# PolarStormControlBoard_smol_275_gnd.net
KiCad netlist of a schematic drawn in EAGLE
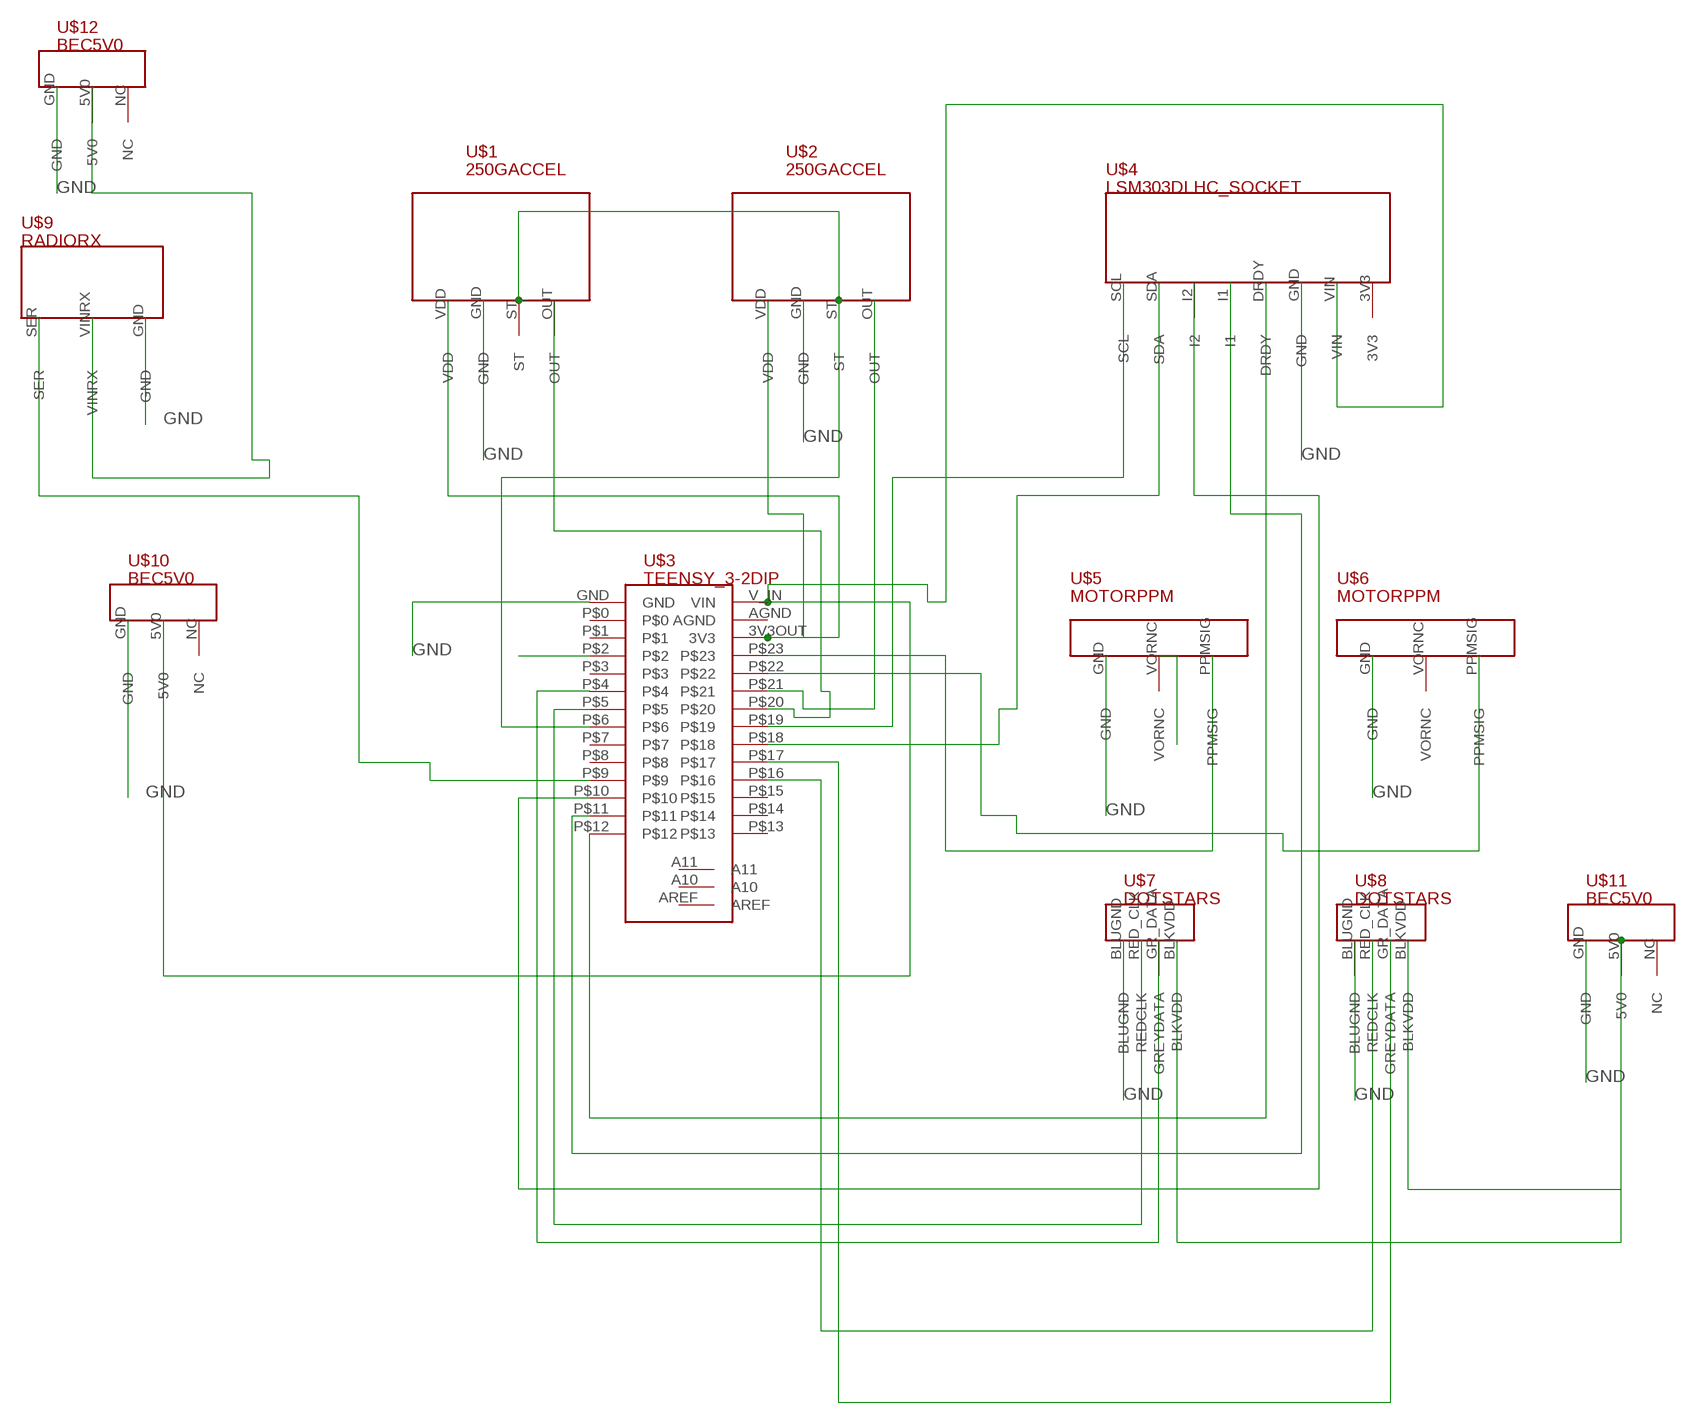
[diagram p0: schematic, sheet 1]

(export (version "E")
  (design (tool "Eeschema 10.0.6"))
  (components
    (comp (ref "U$1")
      (value "250GACCEL")
      (footprint "eagle-import:250GACCEL")
      (libsource (lib "eagle-import") (part "250GACCEL"))
    )
    (comp (ref "U$2")
      (value "250GACCEL")
      (footprint "eagle-import:250GACCEL")
      (libsource (lib "eagle-import") (part "250GACCEL"))
    )
    (comp (ref "U$3")
      (value "TEENSY_3-2DIP")
      (footprint "eagle-import:TEENSY_3_2_SOCKET")
      (libsource (lib "eagle-import") (part "TEENSY_3-2DIP"))
    )
    (comp (ref "U$4")
      (value "LSM303DLHC_SOCKET")
      (footprint "eagle-import:LSM303DLHC_SOCKET")
      (libsource (lib "eagle-import") (part "LSM303DLHC_SOCKET"))
    )
    (comp (ref "U$5")
      (value "MOTORPPM")
      (footprint "eagle-import:MOTORINTERFACE")
      (libsource (lib "eagle-import") (part "MOTORPPM"))
    )
    (comp (ref "U$6")
      (value "MOTORPPM")
      (footprint "eagle-import:MOTORINTERFACE")
      (libsource (lib "eagle-import") (part "MOTORPPM"))
    )
    (comp (ref "U$7")
      (value "DOTSTARS")
      (footprint "eagle-import:DOTSTARHEADER")
      (libsource (lib "eagle-import") (part "DOTSTARS"))
    )
    (comp (ref "U$8")
      (value "DOTSTARS")
      (footprint "eagle-import:DOTSTARHEADER")
      (libsource (lib "eagle-import") (part "DOTSTARS"))
    )
    (comp (ref "U$9")
      (value "RADIORX")
      (footprint "eagle-import:SERIALRX")
      (libsource (lib "eagle-import") (part "RADIORX"))
    )
    (comp (ref "U$10")
      (value "BEC5V0")
      (footprint "eagle-import:BECIN")
      (libsource (lib "eagle-import") (part "BEC5V0"))
    )
    (comp (ref "U$11")
      (value "BEC5V0")
      (footprint "eagle-import:BECIN")
      (libsource (lib "eagle-import") (part "BEC5V0"))
    )
    (comp (ref "U$12")
      (value "BEC5V0")
      (footprint "eagle-import:BECIN")
      (libsource (lib "eagle-import") (part "BEC5V0"))
    )
  )
  (nets
    (net (code "1") (name "/3V3") (class "Default")
      (node (ref "U$4") (pin "3V3") (pinfunction "3V3_3V3") (pintype "power_in"))
    )
    (net (code "2") (name "/GND") (class "Default")
      (node (ref "U$1") (pin "GND") (pinfunction "GND_GND") (pintype "power_in"))
      (node (ref "U$10") (pin "GND") (pinfunction "GND_GND") (pintype "power_in"))
      (node (ref "U$11") (pin "GND") (pinfunction "GND_GND") (pintype "power_in"))
      (node (ref "U$12") (pin "GND") (pinfunction "GND_GND") (pintype "power_in"))
      (node (ref "U$2") (pin "GND") (pinfunction "GND_GND") (pintype "power_in"))
      (node (ref "U$3") (pin "GND") (pinfunction "GND_GND") (pintype "bidirectional"))
      (node (ref "U$4") (pin "GND") (pinfunction "GND_GND") (pintype "power_in"))
      (node (ref "U$5") (pin "GND") (pinfunction "GND_GND") (pintype "power_in"))
      (node (ref "U$6") (pin "GND") (pinfunction "GND_GND") (pintype "power_in"))
      (node (ref "U$7") (pin "BLUGND") (pinfunction "BLUGND_BLUGND") (pintype "power_in"))
      (node (ref "U$8") (pin "BLUGND") (pinfunction "BLUGND_BLUGND") (pintype "power_in"))
      (node (ref "U$9") (pin "GND") (pinfunction "GND_GND") (pintype "power_in"))
    )
    (net (code "3") (name "/VORNC") (class "Default")
      (node (ref "U$6") (pin "VORNC") (pinfunction "VORNC_VORNC") (pintype "power_in"))
    )
    (net (code "4") (name "Net-(U$1-PadOUT)") (class "Default")
      (node (ref "U$1") (pin "OUT") (pinfunction "OUT_OUT") (pintype "output"))
      (node (ref "U$3") (pin "P$20") (pinfunction "P$20_P$20") (pintype "bidirectional"))
    )
    (net (code "5") (name "Net-(U$1-PadST)") (class "Default")
      (node (ref "U$1") (pin "ST") (pinfunction "ST_ST") (pintype "input"))
      (node (ref "U$2") (pin "ST") (pinfunction "ST_ST") (pintype "input"))
      (node (ref "U$3") (pin "P$6") (pinfunction "P$6_P$6") (pintype "bidirectional"))
    )
    (net (code "6") (name "Net-(U$2-PadOUT)") (class "Default")
      (node (ref "U$2") (pin "OUT") (pinfunction "OUT_OUT") (pintype "output"))
      (node (ref "U$3") (pin "P$21") (pinfunction "P$21_P$21") (pintype "bidirectional"))
    )
    (net (code "7") (name "Net-(U$3-3V3)") (class "Default")
      (node (ref "U$1") (pin "VDD") (pinfunction "VDD_VDD") (pintype "power_in"))
      (node (ref "U$2") (pin "VDD") (pinfunction "VDD_VDD") (pintype "power_in"))
      (node (ref "U$3") (pin "3V3OUT") (pinfunction "3V3_3V3OUT") (pintype "bidirectional"))
    )
    (net (code "8") (name "Net-(U$3-PadP$9)") (class "Default")
      (node (ref "U$3") (pin "P$9") (pinfunction "P$9_P$9") (pintype "bidirectional"))
      (node (ref "U$9") (pin "SER") (pinfunction "SER_SER") (pintype "bidirectional"))
    )
    (net (code "9") (name "Net-(U$3-PadP$10)") (class "Default")
      (node (ref "U$3") (pin "P$10") (pinfunction "P$10_P$10") (pintype "bidirectional"))
      (node (ref "U$4") (pin "I2") (pinfunction "I2_I2") (pintype "bidirectional"))
    )
    (net (code "10") (name "Net-(U$3-PadP$11)") (class "Default")
      (node (ref "U$3") (pin "P$11") (pinfunction "P$11_P$11") (pintype "bidirectional"))
      (node (ref "U$4") (pin "I1") (pinfunction "I1_I1") (pintype "bidirectional"))
    )
    (net (code "11") (name "Net-(U$3-PadP$12)") (class "Default")
      (node (ref "U$3") (pin "P$12") (pinfunction "P$12_P$12") (pintype "bidirectional"))
      (node (ref "U$4") (pin "DRDY") (pinfunction "DRDY_DRDY") (pintype "bidirectional"))
    )
    (net (code "12") (name "Net-(U$3-PadP$18)") (class "Default")
      (node (ref "U$3") (pin "P$18") (pinfunction "P$18_P$18") (pintype "bidirectional"))
      (node (ref "U$4") (pin "SDA") (pinfunction "SDA_SDA") (pintype "bidirectional"))
    )
    (net (code "13") (name "Net-(U$3-PadP$19)") (class "Default")
      (node (ref "U$3") (pin "P$19") (pinfunction "P$19_P$19") (pintype "bidirectional"))
      (node (ref "U$4") (pin "SCL") (pinfunction "SCL_SCL") (pintype "bidirectional"))
    )
    (net (code "14") (name "Net-(U$3-PadP$22)") (class "Default")
      (node (ref "U$3") (pin "P$22") (pinfunction "P$22_P$22") (pintype "bidirectional"))
      (node (ref "U$6") (pin "PPMSIG") (pinfunction "PPMSIG_PPMSIG") (pintype "bidirectional"))
    )
    (net (code "15") (name "Net-(U$3-PadP$23)") (class "Default")
      (node (ref "U$3") (pin "P$23") (pinfunction "P$23_P$23") (pintype "bidirectional"))
      (node (ref "U$5") (pin "PPMSIG") (pinfunction "PPMSIG_PPMSIG") (pintype "bidirectional"))
    )
    (net (code "16") (name "Net-(U$3-VIN)") (class "Default")
      (node (ref "U$10") (pin "5V0") (pinfunction "5V0_5V0") (pintype "power_in"))
      (node (ref "U$3") (pin "V_IN") (pinfunction "VIN_V_IN") (pintype "bidirectional"))
      (node (ref "U$4") (pin "VIN") (pinfunction "VIN_VIN") (pintype "power_in"))
    )
    (net (code "17") (name "Net-(U$7-GREYDATA)") (class "Default")
      (node (ref "U$3") (pin "P$4") (pinfunction "P$4_P$4") (pintype "bidirectional"))
      (node (ref "U$7") (pin "GR_DATA") (pinfunction "GREYDATA_GR_DATA") (pintype "bidirectional"))
    )
    (net (code "18") (name "Net-(U$7-REDCLK)") (class "Default")
      (node (ref "U$3") (pin "P$5") (pinfunction "P$5_P$5") (pintype "bidirectional"))
      (node (ref "U$7") (pin "RED_CLK") (pinfunction "REDCLK_RED_CLK") (pintype "bidirectional"))
    )
    (net (code "19") (name "Net-(U$8-GREYDATA)") (class "Default")
      (node (ref "U$3") (pin "P$17") (pinfunction "P$17_P$17") (pintype "bidirectional"))
      (node (ref "U$8") (pin "GR_DATA") (pinfunction "GREYDATA_GR_DATA") (pintype "bidirectional"))
    )
    (net (code "20") (name "Net-(U$8-REDCLK)") (class "Default")
      (node (ref "U$3") (pin "P$16") (pinfunction "P$16_P$16") (pintype "bidirectional"))
      (node (ref "U$8") (pin "RED_CLK") (pinfunction "REDCLK_RED_CLK") (pintype "bidirectional"))
    )
    (net (code "21") (name "Net-(U$11-Pad5V0)") (class "Default")
      (node (ref "U$11") (pin "5V0") (pinfunction "5V0_5V0") (pintype "power_in"))
      (node (ref "U$7") (pin "BLKVDD") (pinfunction "BLKVDD_BLKVDD") (pintype "bidirectional"))
      (node (ref "U$8") (pin "BLKVDD") (pinfunction "BLKVDD_BLKVDD") (pintype "bidirectional"))
    )
    (net (code "22") (name "Net-(U$12-Pad5V0)") (class "Default")
      (node (ref "U$12") (pin "5V0") (pinfunction "5V0_5V0") (pintype "power_in"))
      (node (ref "U$9") (pin "VINRX") (pinfunction "VINRX_VINRX") (pintype "power_in"))
    )
    (net (code "23") (name "unconnected-(U$3-PadA10)") (class "Default")
      (node (ref "U$3") (pin "A10") (pinfunction "A10_A10") (pintype "bidirectional"))
    )
    (net (code "24") (name "unconnected-(U$3-PadA11)") (class "Default")
      (node (ref "U$3") (pin "A11") (pinfunction "A11_A11") (pintype "bidirectional"))
    )
    (net (code "25") (name "unconnected-(U$3-PadAGND)") (class "Default")
      (node (ref "U$3") (pin "AGND") (pinfunction "AGND_AGND") (pintype "bidirectional"))
    )
    (net (code "26") (name "unconnected-(U$3-PadAREF)") (class "Default")
      (node (ref "U$3") (pin "AREF") (pinfunction "AREF_AREF") (pintype "bidirectional"))
    )
    (net (code "27") (name "unconnected-(U$3-PadP$0)") (class "Default")
      (node (ref "U$3") (pin "P$0") (pinfunction "P$0_P$0") (pintype "bidirectional"))
    )
    (net (code "28") (name "unconnected-(U$3-PadP$1)") (class "Default")
      (node (ref "U$3") (pin "P$1") (pinfunction "P$1_P$1") (pintype "bidirectional"))
    )
    (net (code "29") (name "unconnected-(U$3-PadP$2)") (class "Default")
      (node (ref "U$3") (pin "P$2") (pinfunction "P$2_P$2") (pintype "bidirectional"))
    )
    (net (code "30") (name "unconnected-(U$3-PadP$3)") (class "Default")
      (node (ref "U$3") (pin "P$3") (pinfunction "P$3_P$3") (pintype "bidirectional"))
    )
    (net (code "31") (name "unconnected-(U$3-PadP$7)") (class "Default")
      (node (ref "U$3") (pin "P$7") (pinfunction "P$7_P$7") (pintype "bidirectional"))
    )
    (net (code "32") (name "unconnected-(U$3-PadP$8)") (class "Default")
      (node (ref "U$3") (pin "P$8") (pinfunction "P$8_P$8") (pintype "bidirectional"))
    )
    (net (code "33") (name "unconnected-(U$3-PadP$13)") (class "Default")
      (node (ref "U$3") (pin "P$13") (pinfunction "P$13_P$13") (pintype "bidirectional"))
    )
    (net (code "34") (name "unconnected-(U$3-PadP$14)") (class "Default")
      (node (ref "U$3") (pin "P$14") (pinfunction "P$14_P$14") (pintype "bidirectional"))
    )
    (net (code "35") (name "unconnected-(U$3-PadP$15)") (class "Default")
      (node (ref "U$3") (pin "P$15") (pinfunction "P$15_P$15") (pintype "bidirectional"))
    )
    (net (code "36") (name "unconnected-(U$5-PadVORNC)") (class "Default")
      (node (ref "U$5") (pin "VORNC") (pinfunction "VORNC_VORNC") (pintype "power_in"))
    )
    (net (code "37") (name "unconnected-(U$10-PadNC)") (class "Default")
      (node (ref "U$10") (pin "NC") (pinfunction "NC_NC") (pintype "no_connect"))
    )
    (net (code "38") (name "unconnected-(U$11-PadNC)") (class "Default")
      (node (ref "U$11") (pin "NC") (pinfunction "NC_NC") (pintype "no_connect"))
    )
    (net (code "39") (name "unconnected-(U$12-PadNC)") (class "Default")
      (node (ref "U$12") (pin "NC") (pinfunction "NC_NC") (pintype "no_connect"))
    )
  )
)
